# arm_new_v2.net
KiCad netlist of a schematic drawn in EAGLE
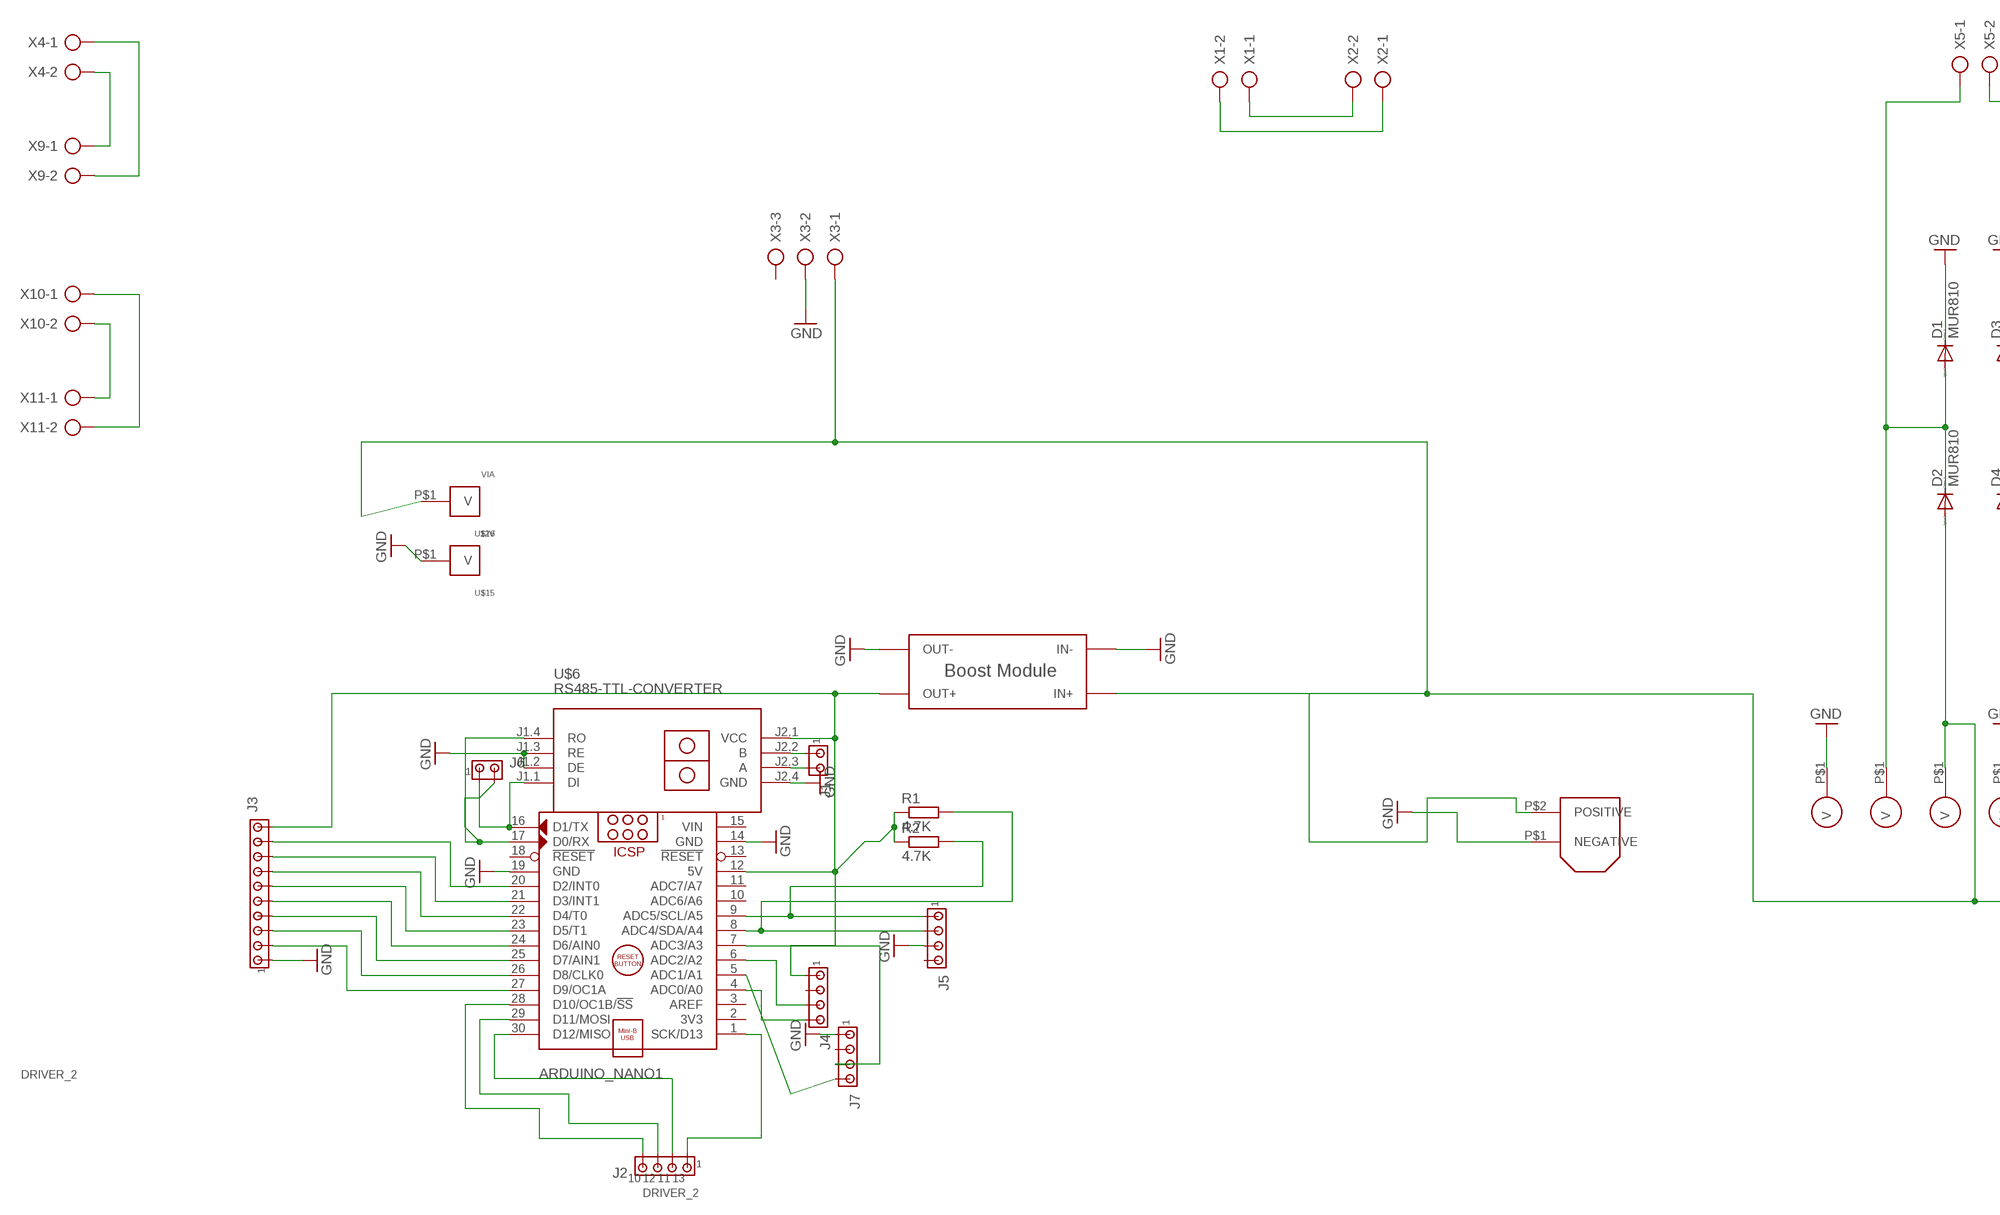
[diagram p0: schematic, sheet 1, part 1 of 2]
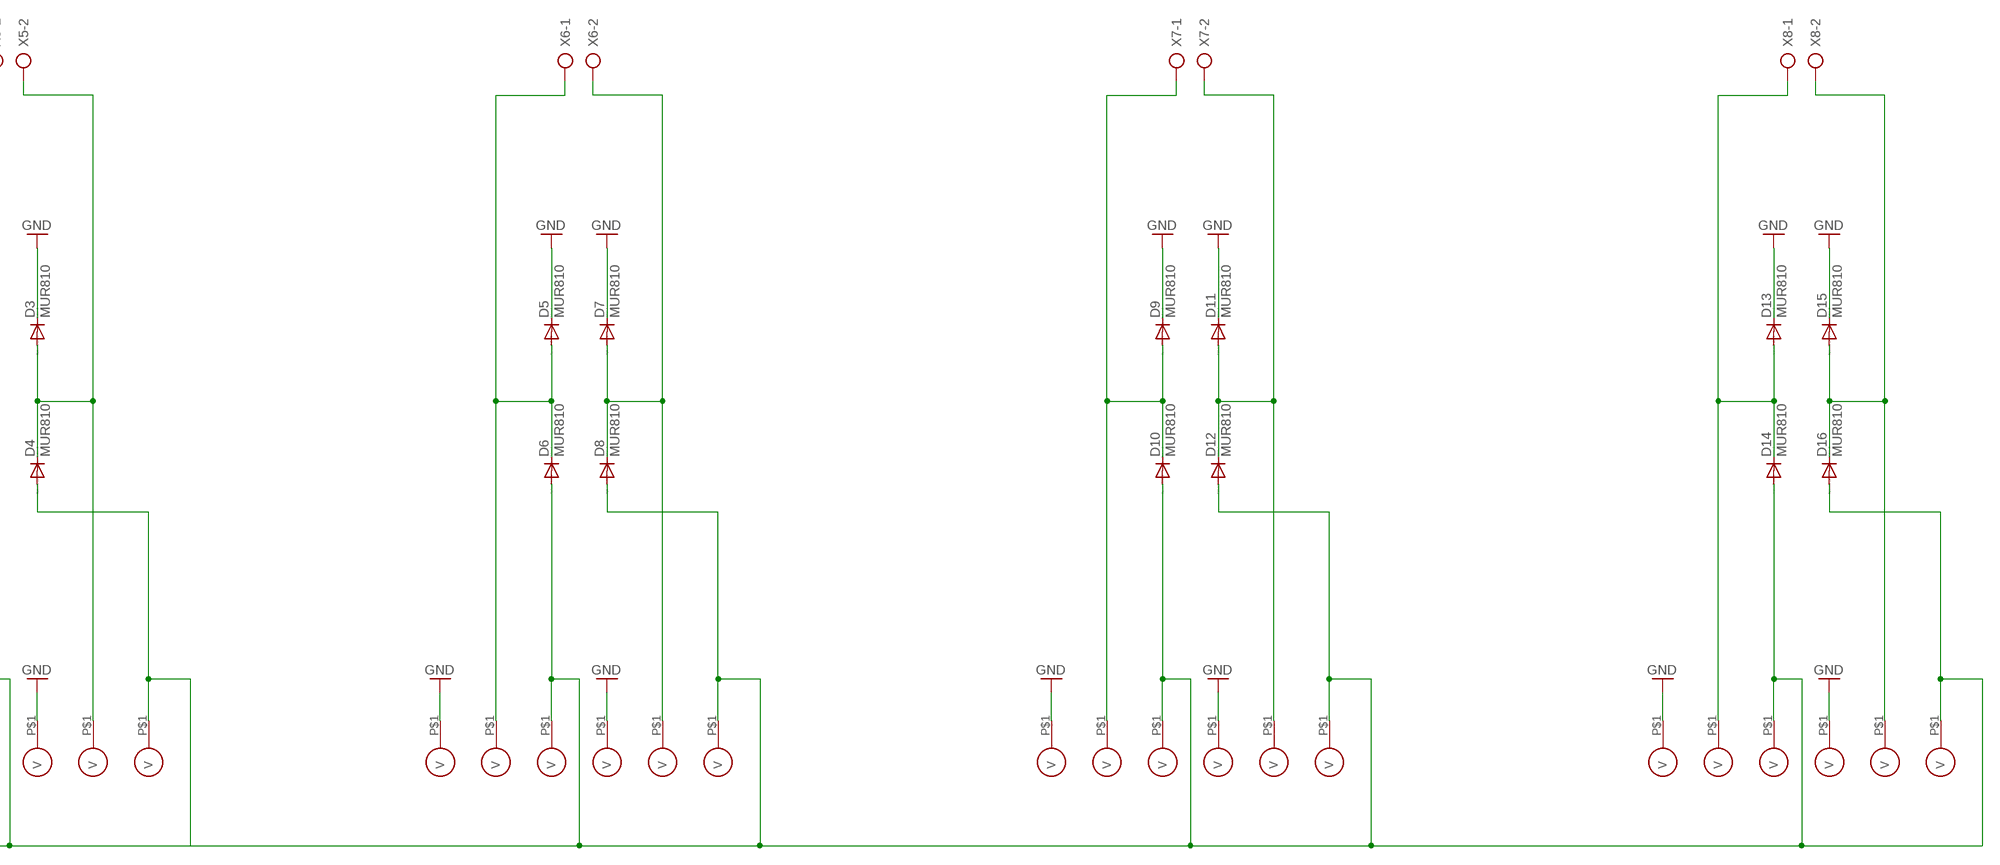
[diagram p1: schematic, sheet 1, part 2 of 2]

(export (version "E")
  (design (tool "Eeschema 10.0.6"))
  (components
    (comp (ref "ARDUINO_NANO1")
      (value "ARDUINO_NANO")
      (footprint "eagle-import:ARDUINO_NANO")
      (libsource (lib "eagle-import") (part "ARDUINO_NANO"))
    )
    (comp (ref "D1")
      (value "MUR810")
      (footprint "eagle-import:TO220ACS")
      (libsource (lib "eagle-import") (part "MUR810"))
    )
    (comp (ref "D2")
      (value "MUR810")
      (footprint "eagle-import:TO220ACS")
      (libsource (lib "eagle-import") (part "MUR810"))
    )
    (comp (ref "D3")
      (value "MUR810")
      (footprint "eagle-import:TO220ACS")
      (libsource (lib "eagle-import") (part "MUR810"))
    )
    (comp (ref "D4")
      (value "MUR810")
      (footprint "eagle-import:TO220ACS")
      (libsource (lib "eagle-import") (part "MUR810"))
    )
    (comp (ref "D5")
      (value "MUR810")
      (footprint "eagle-import:TO220ACS")
      (libsource (lib "eagle-import") (part "MUR810"))
    )
    (comp (ref "D6")
      (value "MUR810")
      (footprint "eagle-import:TO220ACS")
      (libsource (lib "eagle-import") (part "MUR810"))
    )
    (comp (ref "D7")
      (value "MUR810")
      (footprint "eagle-import:TO220ACS")
      (libsource (lib "eagle-import") (part "MUR810"))
    )
    (comp (ref "D8")
      (value "MUR810")
      (footprint "eagle-import:TO220ACS")
      (libsource (lib "eagle-import") (part "MUR810"))
    )
    (comp (ref "D9")
      (value "MUR810")
      (footprint "eagle-import:TO220ACS")
      (libsource (lib "eagle-import") (part "MUR810"))
    )
    (comp (ref "D10")
      (value "MUR810")
      (footprint "eagle-import:TO220ACS")
      (libsource (lib "eagle-import") (part "MUR810"))
    )
    (comp (ref "D11")
      (value "MUR810")
      (footprint "eagle-import:TO220ACS")
      (libsource (lib "eagle-import") (part "MUR810"))
    )
    (comp (ref "D12")
      (value "MUR810")
      (footprint "eagle-import:TO220ACS")
      (libsource (lib "eagle-import") (part "MUR810"))
    )
    (comp (ref "D13")
      (value "MUR810")
      (footprint "eagle-import:TO220ACS")
      (libsource (lib "eagle-import") (part "MUR810"))
    )
    (comp (ref "D14")
      (value "MUR810")
      (footprint "eagle-import:TO220ACS")
      (libsource (lib "eagle-import") (part "MUR810"))
    )
    (comp (ref "D15")
      (value "MUR810")
      (footprint "eagle-import:TO220ACS")
      (libsource (lib "eagle-import") (part "MUR810"))
    )
    (comp (ref "D16")
      (value "MUR810")
      (footprint "eagle-import:TO220ACS")
      (libsource (lib "eagle-import") (part "MUR810"))
    )
    (comp (ref "J1")
      (value "MTA02-100")
      (footprint "eagle-import:10X02MTA")
      (libsource (lib "eagle-import") (part "MTA02-100"))
    )
    (comp (ref "J2")
      (value "MTA04-100")
      (footprint "eagle-import:10X04MTA")
      (libsource (lib "eagle-import") (part "MTA04-100"))
    )
    (comp (ref "J3")
      (value "MTA10-100")
      (footprint "eagle-import:10X10MTA")
      (libsource (lib "eagle-import") (part "MTA10-100"))
    )
    (comp (ref "J4")
      (value "MTA04-100")
      (footprint "eagle-import:10X04MTA")
      (libsource (lib "eagle-import") (part "MTA04-100"))
    )
    (comp (ref "J5")
      (value "MTA04-100")
      (footprint "eagle-import:10X04MTA")
      (libsource (lib "eagle-import") (part "MTA04-100"))
    )
    (comp (ref "J6")
      (value "MTA02-100")
      (footprint "eagle-import:10X02MTA")
      (libsource (lib "eagle-import") (part "MTA02-100"))
    )
    (comp (ref "J7")
      (value "MTA04-100")
      (footprint "eagle-import:10X04MTA")
      (libsource (lib "eagle-import") (part "MTA04-100"))
    )
    (comp (ref "NO")
      (value "NO")
      (footprint "eagle-import:ROUND_VIA")
      (libsource (lib "eagle-import") (part "ROUND_VIA"))
    )
    (comp (ref "NO1")
      (value "NO")
      (footprint "eagle-import:ROUND_VIA")
      (libsource (lib "eagle-import") (part "ROUND_VIA"))
    )
    (comp (ref "NO2")
      (value "NO")
      (footprint "eagle-import:ROUND_VIA")
      (libsource (lib "eagle-import") (part "ROUND_VIA"))
    )
    (comp (ref "NO3")
      (value "NO")
      (footprint "eagle-import:ROUND_VIA")
      (libsource (lib "eagle-import") (part "ROUND_VIA"))
    )
    (comp (ref "R1")
      (value "4.7K")
      (footprint "eagle-import:0204_7")
      (libsource (lib "eagle-import") (part "R-EU_0204/7"))
    )
    (comp (ref "R2")
      (value "4.7K")
      (footprint "eagle-import:0204_7")
      (libsource (lib "eagle-import") (part "R-EU_0204/7"))
    )
    (comp (ref "U$1")
      (value "BOOST_MODULE")
      (footprint "eagle-import:BOOST_MODULE")
      (libsource (lib "eagle-import") (part "BOOST_MODULE"))
    )
    (comp (ref "U$4")
      (value "XT60")
      (footprint "eagle-import:CONNECTOR")
      (libsource (lib "eagle-import") (part "XT60"))
    )
    (comp (ref "U$6")
      (value "RS485-TTL-CONVERTER")
      (footprint "eagle-import:RS485-TTL-CONVERTER")
      (libsource (lib "eagle-import") (part "RS485-TTL-CONVERTER"))
    )
    (comp (ref "U$15")
      (value "12V")
      (footprint "eagle-import:VIA")
      (libsource (lib "eagle-import") (part "VIA"))
    )
    (comp (ref "U$16")
      (value "VIA")
      (footprint "eagle-import:VIA")
      (libsource (lib "eagle-import") (part "VIA"))
    )
    (comp (ref "U$17")
      (value "ROUND_VIA")
      (footprint "eagle-import:ROUND_VIA")
      (libsource (lib "eagle-import") (part "ROUND_VIA"))
    )
    (comp (ref "U$18")
      (value "ROUND_VIA")
      (footprint "eagle-import:ROUND_VIA")
      (libsource (lib "eagle-import") (part "ROUND_VIA"))
    )
    (comp (ref "U$19")
      (value "ROUND_VIA")
      (footprint "eagle-import:ROUND_VIA")
      (libsource (lib "eagle-import") (part "ROUND_VIA"))
    )
    (comp (ref "U$20")
      (value "ROUND_VIA")
      (footprint "eagle-import:ROUND_VIA")
      (libsource (lib "eagle-import") (part "ROUND_VIA"))
    )
    (comp (ref "U$21")
      (value "ROUND_VIA")
      (footprint "eagle-import:ROUND_VIA")
      (libsource (lib "eagle-import") (part "ROUND_VIA"))
    )
    (comp (ref "U$22")
      (value "ROUND_VIA")
      (footprint "eagle-import:ROUND_VIA")
      (libsource (lib "eagle-import") (part "ROUND_VIA"))
    )
    (comp (ref "U$23")
      (value "ROUND_VIA")
      (footprint "eagle-import:ROUND_VIA")
      (libsource (lib "eagle-import") (part "ROUND_VIA"))
    )
    (comp (ref "U$24")
      (value "ROUND_VIA")
      (footprint "eagle-import:ROUND_VIA")
      (libsource (lib "eagle-import") (part "ROUND_VIA"))
    )
    (comp (ref "U$25")
      (value "ROUND_VIA")
      (footprint "eagle-import:ROUND_VIA")
      (libsource (lib "eagle-import") (part "ROUND_VIA"))
    )
    (comp (ref "U$26")
      (value "ROUND_VIA")
      (footprint "eagle-import:ROUND_VIA")
      (libsource (lib "eagle-import") (part "ROUND_VIA"))
    )
    (comp (ref "U$27")
      (value "ROUND_VIA")
      (footprint "eagle-import:ROUND_VIA")
      (libsource (lib "eagle-import") (part "ROUND_VIA"))
    )
    (comp (ref "U$28")
      (value "ROUND_VIA")
      (footprint "eagle-import:ROUND_VIA")
      (libsource (lib "eagle-import") (part "ROUND_VIA"))
    )
    (comp (ref "U$29")
      (value "ROUND_VIA")
      (footprint "eagle-import:ROUND_VIA")
      (libsource (lib "eagle-import") (part "ROUND_VIA"))
    )
    (comp (ref "U$30")
      (value "ROUND_VIA")
      (footprint "eagle-import:ROUND_VIA")
      (libsource (lib "eagle-import") (part "ROUND_VIA"))
    )
    (comp (ref "U$31")
      (value "ROUND_VIA")
      (footprint "eagle-import:ROUND_VIA")
      (libsource (lib "eagle-import") (part "ROUND_VIA"))
    )
    (comp (ref "U$32")
      (value "ROUND_VIA")
      (footprint "eagle-import:ROUND_VIA")
      (libsource (lib "eagle-import") (part "ROUND_VIA"))
    )
    (comp (ref "U$33")
      (value "ROUND_VIA")
      (footprint "eagle-import:ROUND_VIA")
      (libsource (lib "eagle-import") (part "ROUND_VIA"))
    )
    (comp (ref "U$34")
      (value "ROUND_VIA")
      (footprint "eagle-import:ROUND_VIA")
      (libsource (lib "eagle-import") (part "ROUND_VIA"))
    )
    (comp (ref "U$35")
      (value "ROUND_VIA")
      (footprint "eagle-import:ROUND_VIA")
      (libsource (lib "eagle-import") (part "ROUND_VIA"))
    )
    (comp (ref "U$36")
      (value "ROUND_VIA")
      (footprint "eagle-import:ROUND_VIA")
      (libsource (lib "eagle-import") (part "ROUND_VIA"))
    )
    (comp (ref "X1")
      (value "AK300/2")
      (footprint "eagle-import:AK300_2")
      (libsource (lib "eagle-import") (part "AK300/2"))
    )
    (comp (ref "X2")
      (value "AK300/2")
      (footprint "eagle-import:AK300_2")
      (libsource (lib "eagle-import") (part "AK300/2"))
    )
    (comp (ref "X3")
      (value "AK300/3")
      (footprint "eagle-import:AK300_3")
      (libsource (lib "eagle-import") (part "AK300/3"))
    )
    (comp (ref "X4")
      (value "AK300/2")
      (footprint "eagle-import:AK300_2")
      (libsource (lib "eagle-import") (part "AK300/2"))
    )
    (comp (ref "X5")
      (value "AK300/2")
      (footprint "eagle-import:AK300_2")
      (libsource (lib "eagle-import") (part "AK300/2"))
    )
    (comp (ref "X6")
      (value "AK300/2")
      (footprint "eagle-import:AK300_2")
      (libsource (lib "eagle-import") (part "AK300/2"))
    )
    (comp (ref "X7")
      (value "AK300/2")
      (footprint "eagle-import:AK300_2")
      (libsource (lib "eagle-import") (part "AK300/2"))
    )
    (comp (ref "X8")
      (value "AK300/2")
      (footprint "eagle-import:AK300_2")
      (libsource (lib "eagle-import") (part "AK300/2"))
    )
    (comp (ref "X9")
      (value "AK300/2")
      (footprint "eagle-import:AK300_2")
      (libsource (lib "eagle-import") (part "AK300/2"))
    )
    (comp (ref "X10")
      (value "AK300/2")
      (footprint "eagle-import:AK300_2")
      (libsource (lib "eagle-import") (part "AK300/2"))
    )
    (comp (ref "X11")
      (value "AK300/2")
      (footprint "eagle-import:AK300_2")
      (libsource (lib "eagle-import") (part "AK300/2"))
    )
  )
  (nets
    (net (code "1") (name "/VIN") (class "Default")
      (node (ref "ARDUINO_NANO1") (pin "15") (pinfunction "VIN_15") (pintype "power_in"))
    )
    (net (code "2") (name "GND") (class "Default")
      (node (ref "ARDUINO_NANO1") (pin "14") (pinfunction "GND_14") (pintype "power_in"))
      (node (ref "ARDUINO_NANO1") (pin "19") (pinfunction "GND_19") (pintype "power_in"))
      (node (ref "D1") (pin "C") (pinfunction "C_C") (pintype "passive"))
      (node (ref "D11") (pin "C") (pinfunction "C_C") (pintype "passive"))
      (node (ref "D13") (pin "C") (pinfunction "C_C") (pintype "passive"))
      (node (ref "D15") (pin "C") (pinfunction "C_C") (pintype "passive"))
      (node (ref "D3") (pin "C") (pinfunction "C_C") (pintype "passive"))
      (node (ref "D5") (pin "C") (pinfunction "C_C") (pintype "passive"))
      (node (ref "D7") (pin "C") (pinfunction "C_C") (pintype "passive"))
      (node (ref "D9") (pin "C") (pinfunction "C_C") (pintype "passive"))
      (node (ref "J3") (pin "1") (pinfunction "1_1") (pintype "passive"))
      (node (ref "J5") (pin "3") (pinfunction "3_3") (pintype "passive"))
      (node (ref "J7") (pin "1") (pinfunction "1_1") (pintype "passive"))
      (node (ref "NO") (pin "P$1") (pinfunction "V_P$1") (pintype "bidirectional"))
      (node (ref "NO1") (pin "P$1") (pinfunction "V_P$1") (pintype "bidirectional"))
      (node (ref "NO2") (pin "P$1") (pinfunction "V_P$1") (pintype "bidirectional"))
      (node (ref "NO3") (pin "P$1") (pinfunction "V_P$1") (pintype "bidirectional"))
      (node (ref "U$1") (pin "IN-") (pinfunction "IN-_IN-") (pintype "bidirectional"))
      (node (ref "U$1") (pin "OUT-") (pinfunction "OUT-_OUT-") (pintype "bidirectional"))
      (node (ref "U$15") (pin "P$1") (pinfunction "V_P$1") (pintype "bidirectional"))
      (node (ref "U$20") (pin "P$1") (pinfunction "V_P$1") (pintype "bidirectional"))
      (node (ref "U$24") (pin "P$1") (pinfunction "V_P$1") (pintype "bidirectional"))
      (node (ref "U$29") (pin "P$1") (pinfunction "V_P$1") (pintype "bidirectional"))
      (node (ref "U$34") (pin "P$1") (pinfunction "V_P$1") (pintype "bidirectional"))
      (node (ref "U$4") (pin "P$1") (pinfunction "NEGATIVE_P$1") (pintype "bidirectional"))
      (node (ref "U$6") (pin "J1.2") (pinfunction "DE_J1.2") (pintype "passive"))
      (node (ref "U$6") (pin "J1.3") (pinfunction "RE_J1.3") (pintype "passive"))
      (node (ref "U$6") (pin "J2.4") (pinfunction "GND_J2.4") (pintype "power_in"))
      (node (ref "X3") (pin "2") (pinfunction "KL_2") (pintype "passive"))
    )
    (net (code "3") (name "Net-(ARDUINO_NANO1-5V)") (class "Default")
      (node (ref "ARDUINO_NANO1") (pin "12") (pinfunction "5V_12") (pintype "power_in"))
      (node (ref "J3") (pin "10") (pinfunction "10_10") (pintype "passive"))
      (node (ref "J4") (pin "1") (pinfunction "1_1") (pintype "passive"))
      (node (ref "R1") (pin "1") (pinfunction "1_1") (pintype "passive"))
      (node (ref "R2") (pin "1") (pinfunction "1_1") (pintype "passive"))
      (node (ref "U$1") (pin "OUT+") (pinfunction "OUT+_OUT+") (pintype "bidirectional"))
      (node (ref "U$6") (pin "J2.1") (pinfunction "VCC_J2.1") (pintype "power_in"))
    )
    (net (code "4") (name "Net-(ARDUINO_NANO1-ADC0{slash}A0)") (class "Default")
      (node (ref "ARDUINO_NANO1") (pin "4") (pinfunction "ADC0/A0_4") (pintype "bidirectional"))
      (node (ref "J4") (pin "4") (pinfunction "4_4") (pintype "passive"))
    )
    (net (code "5") (name "Net-(ARDUINO_NANO1-ADC1{slash}A1)") (class "Default")
      (node (ref "ARDUINO_NANO1") (pin "5") (pinfunction "ADC1/A1_5") (pintype "bidirectional"))
      (node (ref "J7") (pin "4") (pinfunction "4_4") (pintype "passive"))
    )
    (net (code "6") (name "Net-(ARDUINO_NANO1-ADC2{slash}A2)") (class "Default")
      (node (ref "ARDUINO_NANO1") (pin "6") (pinfunction "ADC2/A2_6") (pintype "bidirectional"))
      (node (ref "J4") (pin "3") (pinfunction "3_3") (pintype "passive"))
    )
    (net (code "7") (name "Net-(ARDUINO_NANO1-ADC3{slash}A3)") (class "Default")
      (node (ref "ARDUINO_NANO1") (pin "7") (pinfunction "ADC3/A3_7") (pintype "bidirectional"))
      (node (ref "J7") (pin "3") (pinfunction "3_3") (pintype "passive"))
    )
    (net (code "8") (name "Net-(ARDUINO_NANO1-ADC4{slash}SDA{slash}A4)") (class "Default")
      (node (ref "ARDUINO_NANO1") (pin "8") (pinfunction "ADC4/SDA/A4_8") (pintype "bidirectional"))
      (node (ref "J5") (pin "2") (pinfunction "2_2") (pintype "passive"))
      (node (ref "R1") (pin "2") (pinfunction "2_2") (pintype "passive"))
    )
    (net (code "9") (name "Net-(ARDUINO_NANO1-ADC5{slash}SCL{slash}A5)") (class "Default")
      (node (ref "ARDUINO_NANO1") (pin "9") (pinfunction "ADC5/SCL/A5_9") (pintype "bidirectional"))
      (node (ref "J5") (pin "1") (pinfunction "1_1") (pintype "passive"))
      (node (ref "R2") (pin "2") (pinfunction "2_2") (pintype "passive"))
    )
    (net (code "10") (name "Net-(ARDUINO_NANO1-D0{slash}RX)") (class "Default")
      (node (ref "ARDUINO_NANO1") (pin "17") (pinfunction "D0/RX_17") (pintype "bidirectional"))
      (node (ref "J6") (pin "2") (pinfunction "2_2") (pintype "passive"))
      (node (ref "U$6") (pin "J1.4") (pinfunction "RO_J1.4") (pintype "passive"))
    )
    (net (code "11") (name "Net-(ARDUINO_NANO1-D1{slash}TX)") (class "Default")
      (node (ref "ARDUINO_NANO1") (pin "16") (pinfunction "D1/TX_16") (pintype "bidirectional"))
      (node (ref "J6") (pin "1") (pinfunction "1_1") (pintype "passive"))
      (node (ref "U$6") (pin "J1.1") (pinfunction "DI_J1.1") (pintype "passive"))
    )
    (net (code "12") (name "Net-(ARDUINO_NANO1-D2{slash}INT0)") (class "Default")
      (node (ref "ARDUINO_NANO1") (pin "20") (pinfunction "D2/INT0_20") (pintype "bidirectional"))
      (node (ref "J3") (pin "9") (pinfunction "9_9") (pintype "passive"))
    )
    (net (code "13") (name "Net-(ARDUINO_NANO1-D3{slash}INT1)") (class "Default")
      (node (ref "ARDUINO_NANO1") (pin "21") (pinfunction "D3/INT1_21") (pintype "bidirectional"))
      (node (ref "J3") (pin "8") (pinfunction "8_8") (pintype "passive"))
    )
    (net (code "14") (name "Net-(ARDUINO_NANO1-D4{slash}T0)") (class "Default")
      (node (ref "ARDUINO_NANO1") (pin "22") (pinfunction "D4/T0_22") (pintype "bidirectional"))
      (node (ref "J3") (pin "7") (pinfunction "7_7") (pintype "passive"))
    )
    (net (code "15") (name "Net-(ARDUINO_NANO1-D5{slash}T1)") (class "Default")
      (node (ref "ARDUINO_NANO1") (pin "23") (pinfunction "D5/T1_23") (pintype "bidirectional"))
      (node (ref "J3") (pin "6") (pinfunction "6_6") (pintype "passive"))
    )
    (net (code "16") (name "Net-(ARDUINO_NANO1-D6{slash}AIN0)") (class "Default")
      (node (ref "ARDUINO_NANO1") (pin "24") (pinfunction "D6/AIN0_24") (pintype "bidirectional"))
      (node (ref "J3") (pin "5") (pinfunction "5_5") (pintype "passive"))
    )
    (net (code "17") (name "Net-(ARDUINO_NANO1-D7{slash}AIN1)") (class "Default")
      (node (ref "ARDUINO_NANO1") (pin "25") (pinfunction "D7/AIN1_25") (pintype "bidirectional"))
      (node (ref "J3") (pin "4") (pinfunction "4_4") (pintype "passive"))
    )
    (net (code "18") (name "Net-(ARDUINO_NANO1-D8{slash}CLK0)") (class "Default")
      (node (ref "ARDUINO_NANO1") (pin "26") (pinfunction "D8/CLK0_26") (pintype "bidirectional"))
      (node (ref "J3") (pin "3") (pinfunction "3_3") (pintype "passive"))
    )
    (net (code "19") (name "Net-(ARDUINO_NANO1-D9{slash}OC1A)") (class "Default")
      (node (ref "ARDUINO_NANO1") (pin "27") (pinfunction "D9/OC1A_27") (pintype "bidirectional"))
      (node (ref "J3") (pin "2") (pinfunction "2_2") (pintype "passive"))
    )
    (net (code "20") (name "Net-(ARDUINO_NANO1-D10{slash}OC1B{slash}~{SS})") (class "Default")
      (node (ref "ARDUINO_NANO1") (pin "28") (pinfunction "D10/OC1B/~{SS}_28") (pintype "bidirectional"))
      (node (ref "J2") (pin "4") (pinfunction "4_4") (pintype "passive"))
    )
    (net (code "21") (name "Net-(ARDUINO_NANO1-D11{slash}MOSI)") (class "Default")
      (node (ref "ARDUINO_NANO1") (pin "29") (pinfunction "D11/MOSI_29") (pintype "bidirectional"))
      (node (ref "J2") (pin "3") (pinfunction "3_3") (pintype "passive"))
    )
    (net (code "22") (name "Net-(ARDUINO_NANO1-D12{slash}MISO)") (class "Default")
      (node (ref "ARDUINO_NANO1") (pin "30") (pinfunction "D12/MISO_30") (pintype "bidirectional"))
      (node (ref "J2") (pin "2") (pinfunction "2_2") (pintype "passive"))
    )
    (net (code "23") (name "Net-(ARDUINO_NANO1-SCK{slash}D13)") (class "Default")
      (node (ref "ARDUINO_NANO1") (pin "1") (pinfunction "SCK/D13_1") (pintype "bidirectional"))
      (node (ref "J2") (pin "1") (pinfunction "1_1") (pintype "passive"))
    )
    (net (code "24") (name "Net-(U$6-A)") (class "Default")
      (node (ref "J1") (pin "2") (pinfunction "2_2") (pintype "passive"))
      (node (ref "U$6") (pin "J2.3") (pinfunction "A_J2.3") (pintype "passive"))
    )
    (net (code "25") (name "Net-(U$6-B)") (class "Default")
      (node (ref "J1") (pin "1") (pinfunction "1_1") (pintype "passive"))
      (node (ref "U$6") (pin "J2.2") (pinfunction "B_J2.2") (pintype "passive"))
    )
    (net (code "26") (name "Net-(U$16-V)") (class "Default")
      (node (ref "D10") (pin "A") (pinfunction "A_A") (pintype "passive"))
      (node (ref "D12") (pin "A") (pinfunction "A_A") (pintype "passive"))
      (node (ref "D14") (pin "A") (pinfunction "A_A") (pintype "passive"))
      (node (ref "D16") (pin "A") (pinfunction "A_A") (pintype "passive"))
      (node (ref "D2") (pin "A") (pinfunction "A_A") (pintype "passive"))
      (node (ref "D4") (pin "A") (pinfunction "A_A") (pintype "passive"))
      (node (ref "D6") (pin "A") (pinfunction "A_A") (pintype "passive"))
      (node (ref "D8") (pin "A") (pinfunction "A_A") (pintype "passive"))
      (node (ref "U$1") (pin "IN+") (pinfunction "IN+_IN+") (pintype "bidirectional"))
      (node (ref "U$16") (pin "P$1") (pinfunction "V_P$1") (pintype "bidirectional"))
      (node (ref "U$19") (pin "P$1") (pinfunction "V_P$1") (pintype "bidirectional"))
      (node (ref "U$22") (pin "P$1") (pinfunction "V_P$1") (pintype "bidirectional"))
      (node (ref "U$23") (pin "P$1") (pinfunction "V_P$1") (pintype "bidirectional"))
      (node (ref "U$26") (pin "P$1") (pinfunction "V_P$1") (pintype "bidirectional"))
      (node (ref "U$28") (pin "P$1") (pinfunction "V_P$1") (pintype "bidirectional"))
      (node (ref "U$31") (pin "P$1") (pinfunction "V_P$1") (pintype "bidirectional"))
      (node (ref "U$33") (pin "P$1") (pinfunction "V_P$1") (pintype "bidirectional"))
      (node (ref "U$36") (pin "P$1") (pinfunction "V_P$1") (pintype "bidirectional"))
      (node (ref "U$4") (pin "P$2") (pinfunction "POSITIVE_P$2") (pintype "bidirectional"))
      (node (ref "X3") (pin "1") (pinfunction "KL_1") (pintype "passive"))
    )
    (net (code "27") (name "Net-(U$17-V)") (class "Default")
      (node (ref "D5") (pin "A") (pinfunction "A_A") (pintype "passive"))
      (node (ref "D6") (pin "C") (pinfunction "C_C") (pintype "passive"))
      (node (ref "U$17") (pin "P$1") (pinfunction "V_P$1") (pintype "bidirectional"))
      (node (ref "X6") (pin "1") (pinfunction "KL_1") (pintype "passive"))
    )
    (net (code "28") (name "Net-(U$18-V)") (class "Default")
      (node (ref "D1") (pin "A") (pinfunction "A_A") (pintype "passive"))
      (node (ref "D2") (pin "C") (pinfunction "C_C") (pintype "passive"))
      (node (ref "U$18") (pin "P$1") (pinfunction "V_P$1") (pintype "bidirectional"))
      (node (ref "X5") (pin "1") (pinfunction "KL_1") (pintype "passive"))
    )
    (net (code "29") (name "Net-(U$21-V)") (class "Default")
      (node (ref "D3") (pin "A") (pinfunction "A_A") (pintype "passive"))
      (node (ref "D4") (pin "C") (pinfunction "C_C") (pintype "passive"))
      (node (ref "U$21") (pin "P$1") (pinfunction "V_P$1") (pintype "bidirectional"))
      (node (ref "X5") (pin "2") (pinfunction "KL_2") (pintype "passive"))
    )
    (net (code "30") (name "Net-(U$25-V)") (class "Default")
      (node (ref "D7") (pin "A") (pinfunction "A_A") (pintype "passive"))
      (node (ref "D8") (pin "C") (pinfunction "C_C") (pintype "passive"))
      (node (ref "U$25") (pin "P$1") (pinfunction "V_P$1") (pintype "bidirectional"))
      (node (ref "X6") (pin "2") (pinfunction "KL_2") (pintype "passive"))
    )
    (net (code "31") (name "Net-(U$27-V)") (class "Default")
      (node (ref "D10") (pin "C") (pinfunction "C_C") (pintype "passive"))
      (node (ref "D9") (pin "A") (pinfunction "A_A") (pintype "passive"))
      (node (ref "U$27") (pin "P$1") (pinfunction "V_P$1") (pintype "bidirectional"))
      (node (ref "X7") (pin "1") (pinfunction "KL_1") (pintype "passive"))
    )
    (net (code "32") (name "Net-(U$30-V)") (class "Default")
      (node (ref "D11") (pin "A") (pinfunction "A_A") (pintype "passive"))
      (node (ref "D12") (pin "C") (pinfunction "C_C") (pintype "passive"))
      (node (ref "U$30") (pin "P$1") (pinfunction "V_P$1") (pintype "bidirectional"))
      (node (ref "X7") (pin "2") (pinfunction "KL_2") (pintype "passive"))
    )
    (net (code "33") (name "Net-(U$32-V)") (class "Default")
      (node (ref "D13") (pin "A") (pinfunction "A_A") (pintype "passive"))
      (node (ref "D14") (pin "C") (pinfunction "C_C") (pintype "passive"))
      (node (ref "U$32") (pin "P$1") (pinfunction "V_P$1") (pintype "bidirectional"))
      (node (ref "X8") (pin "1") (pinfunction "KL_1") (pintype "passive"))
    )
    (net (code "34") (name "Net-(U$35-V)") (class "Default")
      (node (ref "D15") (pin "A") (pinfunction "A_A") (pintype "passive"))
      (node (ref "D16") (pin "C") (pinfunction "C_C") (pintype "passive"))
      (node (ref "U$35") (pin "P$1") (pinfunction "V_P$1") (pintype "bidirectional"))
      (node (ref "X8") (pin "2") (pinfunction "KL_2") (pintype "passive"))
    )
    (net (code "35") (name "Net-(X1A-KL)") (class "Default")
      (node (ref "X1") (pin "1") (pinfunction "KL_1") (pintype "passive"))
      (node (ref "X2") (pin "2") (pinfunction "KL_2") (pintype "passive"))
    )
    (net (code "36") (name "Net-(X1B-KL)") (class "Default")
      (node (ref "X1") (pin "2") (pinfunction "KL_2") (pintype "passive"))
      (node (ref "X2") (pin "1") (pinfunction "KL_1") (pintype "passive"))
    )
    (net (code "37") (name "Net-(X4A-KL)") (class "Default")
      (node (ref "X4") (pin "1") (pinfunction "KL_1") (pintype "passive"))
      (node (ref "X9") (pin "2") (pinfunction "KL_2") (pintype "passive"))
    )
    (net (code "38") (name "Net-(X4B-KL)") (class "Default")
      (node (ref "X4") (pin "2") (pinfunction "KL_2") (pintype "passive"))
      (node (ref "X9") (pin "1") (pinfunction "KL_1") (pintype "passive"))
    )
    (net (code "39") (name "Net-(X10A-KL)") (class "Default")
      (node (ref "X10") (pin "1") (pinfunction "KL_1") (pintype "passive"))
      (node (ref "X11") (pin "2") (pinfunction "KL_2") (pintype "passive"))
    )
    (net (code "40") (name "Net-(X10B-KL)") (class "Default")
      (node (ref "X10") (pin "2") (pinfunction "KL_2") (pintype "passive"))
      (node (ref "X11") (pin "1") (pinfunction "KL_1") (pintype "passive"))
    )
    (net (code "41") (name "unconnected-(ARDUINO_NANO1-3V3-Pad2)") (class "Default")
      (node (ref "ARDUINO_NANO1") (pin "2") (pinfunction "3V3_2") (pintype "output"))
    )
    (net (code "42") (name "unconnected-(ARDUINO_NANO1-ADC6{slash}A6-Pad10)") (class "Default")
      (node (ref "ARDUINO_NANO1") (pin "10") (pinfunction "ADC6/A6_10") (pintype "bidirectional"))
    )
    (net (code "43") (name "unconnected-(ARDUINO_NANO1-ADC7{slash}A7-Pad11)") (class "Default")
      (node (ref "ARDUINO_NANO1") (pin "11") (pinfunction "ADC7/A7_11") (pintype "bidirectional"))
    )
    (net (code "44") (name "unconnected-(ARDUINO_NANO1-AREF-Pad3)") (class "Default")
      (node (ref "ARDUINO_NANO1") (pin "3") (pinfunction "AREF_3") (pintype "input"))
    )
    (net (code "45") (name "unconnected-(ARDUINO_NANO1-~{RESET}-Pad13)") (class "Default")
      (node (ref "ARDUINO_NANO1") (pin "13") (pinfunction "~{RESET}_13") (pintype "input"))
    )
    (net (code "46") (name "unconnected-(ARDUINO_NANO1-~{RESET}-Pad18)") (class "Default")
      (node (ref "ARDUINO_NANO1") (pin "18") (pinfunction "~{RESET}_18") (pintype "input"))
    )
    (net (code "47") (name "unconnected-(J4-Pad2)") (class "Default")
      (node (ref "J4") (pin "2") (pinfunction "2_2") (pintype "passive"))
    )
    (net (code "48") (name "unconnected-(J5-Pad4)") (class "Default")
      (node (ref "J5") (pin "4") (pinfunction "4_4") (pintype "passive"))
    )
    (net (code "49") (name "unconnected-(J7-Pad2)") (class "Default")
      (node (ref "J7") (pin "2") (pinfunction "2_2") (pintype "passive"))
    )
    (net (code "50") (name "unconnected-(X3C-KL-Pad3)") (class "Default")
      (node (ref "X3") (pin "3") (pinfunction "KL_3") (pintype "passive"))
    )
  )
)
